# LED.net
KiCad netlist of a schematic drawn in Altium Designer
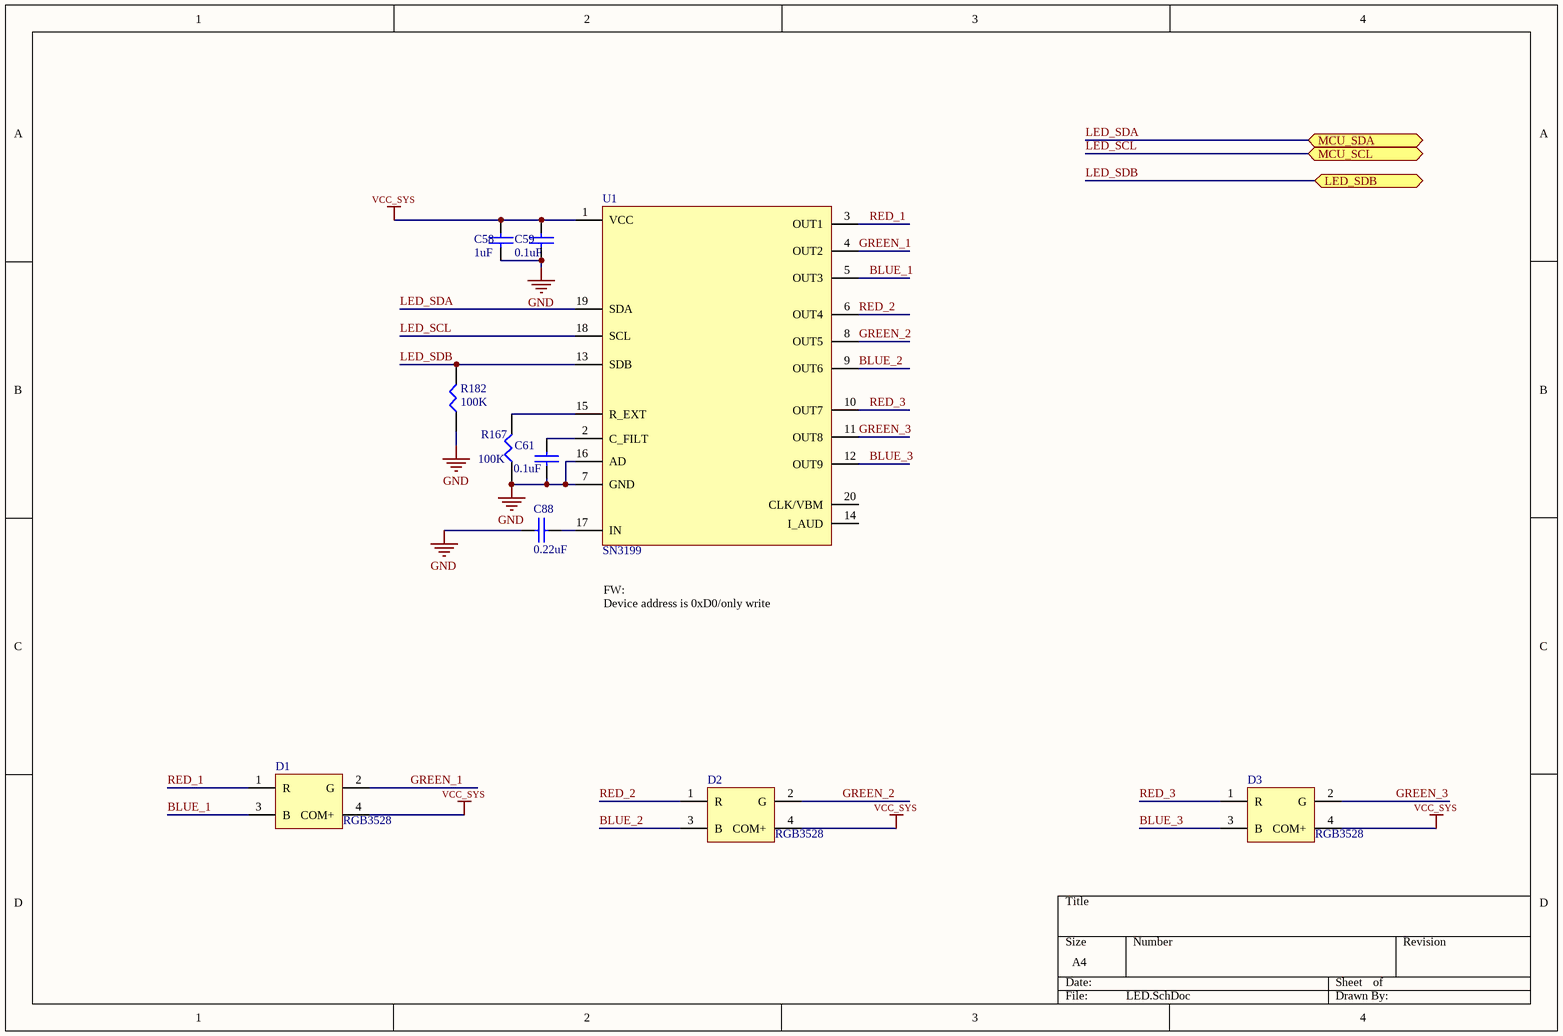
[diagram p0: LED.SchDoc]

(export (version "E")
  (design (tool "Eeschema 10.0.6"))
  (components
    (comp (ref "C58")
      (value "1uF")
      (footprint "0402C")
      (description "1uF/10V/X7R/10%，0402")
      (libsource (lib "Schlib1") (part "CAP"))
    )
    (comp (ref "C59")
      (value "0.1uF")
      (footprint "0402C")
      (description "0.1uF/10V/X7R/10%，0402")
      (libsource (lib "Schlib1") (part "CAP"))
    )
    (comp (ref "C61")
      (value "0.1uF")
      (footprint "0402C")
      (description "0.1uF/10V/X7R/10%，0402")
      (libsource (lib "Schlib1") (part "CAP"))
    )
    (comp (ref "C88")
      (value "0.22uF")
      (footprint "0402C")
      (description "0.22uF/10V/X7R/10%，0402")
      (libsource (lib "Schlib1") (part "CAP"))
    )
    (comp (ref "D1")
      (value "RGB3528")
      (footprint "R6GHBHC")
      (fields (field (name "PUBLISHER") "Altium Limited"))
      (libsource (lib "常用sch库") (part "RGB3528"))
    )
    (comp (ref "D2")
      (value "RGB3528")
      (footprint "R6GHBHC")
      (fields (field (name "PUBLISHER") "Altium Limited"))
      (libsource (lib "常用sch库") (part "RGB3528"))
    )
    (comp (ref "D3")
      (value "RGB3528")
      (footprint "R6GHBHC")
      (fields (field (name "PUBLISHER") "Altium Limited"))
      (libsource (lib "常用sch库") (part "RGB3528"))
    )
    (comp (ref "R167")
      (value "100K")
      (footprint "0402R")
      (description "100K/5%，0402")
      (libsource (lib "Schlib1") (part "RES"))
    )
    (comp (ref "R182")
      (value "100K")
      (footprint "0402R")
      (description "100K/5%，0402")
      (libsource (lib "Schlib1") (part "RES"))
    )
    (comp (ref "U1")
      (value "SN3199")
      (footprint "QFN20-B")
      (description "厂家：SI-EN，型号：IS31FL3199-QFLS2-TR")
      (libsource (lib "Centrol Control Panel") (part "SN3199"))
    )
  )
  (nets
    (net (code "1") (name "/BLUE_1") (class "Default")
      (node (ref "D1") (pin "3") (pinfunction "B_3") (pintype "passive"))
      (node (ref "U1") (pin "5") (pinfunction "OUT3_5") (pintype "passive"))
    )
    (net (code "2") (name "/BLUE_2") (class "Default")
      (node (ref "D2") (pin "3") (pinfunction "B_3") (pintype "passive"))
      (node (ref "U1") (pin "9") (pinfunction "OUT6_9") (pintype "passive"))
    )
    (net (code "3") (name "/BLUE_3") (class "Default")
      (node (ref "D3") (pin "3") (pinfunction "B_3") (pintype "passive"))
      (node (ref "U1") (pin "12") (pinfunction "OUT9_12") (pintype "passive"))
    )
    (net (code "4") (name "/GREEN_1") (class "Default")
      (node (ref "D1") (pin "2") (pinfunction "G_2") (pintype "passive"))
      (node (ref "U1") (pin "4") (pinfunction "OUT2_4") (pintype "passive"))
    )
    (net (code "5") (name "/GREEN_2") (class "Default")
      (node (ref "D2") (pin "2") (pinfunction "G_2") (pintype "passive"))
      (node (ref "U1") (pin "8") (pinfunction "OUT5_8") (pintype "passive"))
    )
    (net (code "6") (name "/GREEN_3") (class "Default")
      (node (ref "D3") (pin "2") (pinfunction "G_2") (pintype "passive"))
      (node (ref "U1") (pin "11") (pinfunction "OUT8_11") (pintype "passive"))
    )
    (net (code "7") (name "/LED_SCL") (class "Default")
      (node (ref "U1") (pin "18") (pinfunction "SCL_18") (pintype "passive"))
    )
    (net (code "8") (name "/LED_SDA") (class "Default")
      (node (ref "U1") (pin "19") (pinfunction "SDA_19") (pintype "passive"))
    )
    (net (code "9") (name "/LED_SDB") (class "Default")
      (node (ref "R182") (pin "2") (pinfunction "2_2") (pintype "passive"))
      (node (ref "U1") (pin "13") (pinfunction "SDB_13") (pintype "passive"))
    )
    (net (code "10") (name "/RED_1") (class "Default")
      (node (ref "D1") (pin "1") (pinfunction "R_1") (pintype "passive"))
      (node (ref "U1") (pin "3") (pinfunction "OUT1_3") (pintype "passive"))
    )
    (net (code "11") (name "/RED_2") (class "Default")
      (node (ref "D2") (pin "1") (pinfunction "R_1") (pintype "passive"))
      (node (ref "U1") (pin "6") (pinfunction "OUT4_6") (pintype "passive"))
    )
    (net (code "12") (name "/RED_3") (class "Default")
      (node (ref "D3") (pin "1") (pinfunction "R_1") (pintype "passive"))
      (node (ref "U1") (pin "10") (pinfunction "OUT7_10") (pintype "passive"))
    )
    (net (code "13") (name "GND") (class "Default")
      (node (ref "C58") (pin "2") (pinfunction "2_2") (pintype "passive"))
      (node (ref "C59") (pin "2") (pinfunction "2_2") (pintype "passive"))
      (node (ref "C61") (pin "2") (pinfunction "2_2") (pintype "passive"))
      (node (ref "C88") (pin "1") (pinfunction "1_1") (pintype "passive"))
      (node (ref "R167") (pin "1") (pinfunction "1_1") (pintype "passive"))
      (node (ref "R182") (pin "1") (pinfunction "1_1") (pintype "passive"))
      (node (ref "U1") (pin "16") (pinfunction "AD_16") (pintype "passive"))
      (node (ref "U1") (pin "7") (pinfunction "GND_7") (pintype "passive"))
    )
    (net (code "14") (name "Net-(U1-C_FILT)") (class "Default")
      (node (ref "C61") (pin "1") (pinfunction "1_1") (pintype "passive"))
      (node (ref "U1") (pin "2") (pinfunction "C_FILT_2") (pintype "passive"))
    )
    (net (code "15") (name "Net-(U1-IN)") (class "Default")
      (node (ref "C88") (pin "2") (pinfunction "2_2") (pintype "passive"))
      (node (ref "U1") (pin "17") (pinfunction "IN_17") (pintype "passive"))
    )
    (net (code "16") (name "Net-(U1-R_EXT)") (class "Default")
      (node (ref "R167") (pin "2") (pinfunction "2_2") (pintype "passive"))
      (node (ref "U1") (pin "15") (pinfunction "R_EXT_15") (pintype "passive"))
    )
    (net (code "17") (name "VCC_SYS") (class "Default")
      (node (ref "C58") (pin "1") (pinfunction "1_1") (pintype "passive"))
      (node (ref "C59") (pin "1") (pinfunction "1_1") (pintype "passive"))
      (node (ref "D1") (pin "4") (pinfunction "COM+_4") (pintype "passive"))
      (node (ref "D2") (pin "4") (pinfunction "COM+_4") (pintype "passive"))
      (node (ref "D3") (pin "4") (pinfunction "COM+_4") (pintype "passive"))
      (node (ref "U1") (pin "1") (pinfunction "VCC_1") (pintype "passive"))
    )
    (net (code "18") (name "unconnected-(U1-CLK{slash}VBM-Pad20)") (class "Default")
      (node (ref "U1") (pin "20") (pinfunction "CLK/VBM_20") (pintype "passive"))
    )
    (net (code "19") (name "unconnected-(U1-I_AUD-Pad14)") (class "Default")
      (node (ref "U1") (pin "14") (pinfunction "I_AUD_14") (pintype "passive"))
    )
  )
)
